# SENSORS.net
KiCad netlist of a schematic drawn in Altium Designer
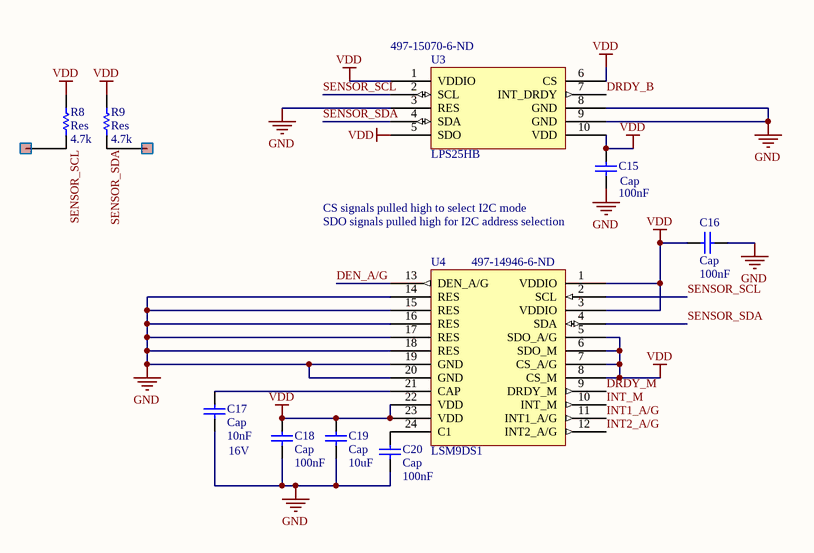
[diagram p0: SENSORS.SchDoc]

(export (version "E")
  (design (tool "Eeschema 10.0.6"))
  (components
    (comp (ref "C15")
      (value "Cap")
      (footprint "C0805")
      (description "Capacitor")
      (fields (field (name "ALTIUM_VALUE") "100nF") (field (name "PUBLISHER") "Altium Limited"))
      (libsource (lib "Capacitors") (part "Cap"))
    )
    (comp (ref "C16")
      (value "Cap")
      (footprint "C0805")
      (description "Capacitor")
      (fields (field (name "ALTIUM_VALUE") "100nF") (field (name "PUBLISHER") "Altium Limited"))
      (libsource (lib "Capacitors") (part "Cap"))
    )
    (comp (ref "C17")
      (value "Cap")
      (footprint "C0805")
      (description "Capacitor")
      (fields
        (field (name "ALTIUM_VALUE") "10nF")
        (field (name "RATING") "16V")
        (field (name "PUBLISHER") "Altium Limited")
      )
      (libsource (lib "Capacitors") (part "Cap"))
    )
    (comp (ref "C18")
      (value "Cap")
      (footprint "C0805")
      (description "Capacitor")
      (fields (field (name "ALTIUM_VALUE") "100nF") (field (name "PUBLISHER") "Altium Limited"))
      (libsource (lib "Capacitors") (part "Cap"))
    )
    (comp (ref "C19")
      (value "Cap")
      (footprint "C0805")
      (description "Capacitor")
      (fields (field (name "ALTIUM_VALUE") "10uF") (field (name "PUBLISHER") "Altium Limited"))
      (libsource (lib "Capacitors") (part "Cap"))
    )
    (comp (ref "C20")
      (value "Cap")
      (footprint "C0805")
      (description "Capacitor")
      (fields (field (name "ALTIUM_VALUE") "100nF") (field (name "PUBLISHER") "Altium Limited"))
      (libsource (lib "Capacitors") (part "Cap"))
    )
    (comp (ref "R8")
      (value "Res")
      (footprint "3216[1206]")
      (description "Surface Mount Resistor")
      (fields (field (name "ALTIUM_VALUE") "4.7k") (field (name "PUBLISHER") "Altium Limited"))
      (libsource (lib "Resistors") (part "Res"))
    )
    (comp (ref "R9")
      (value "Res")
      (footprint "3216[1206]")
      (description "Surface Mount Resistor")
      (fields (field (name "ALTIUM_VALUE") "4.7k") (field (name "PUBLISHER") "Altium Limited"))
      (libsource (lib "Resistors") (part "Res"))
    )
    (comp (ref "TPS1")
      (value "Test_point_SMD")
      (footprint "TEST_POINT_SMD")
      (description "Test Point SMD")
      (libsource (lib "FC") (part "Test_point_SMD"))
    )
    (comp (ref "TPS2")
      (value "Test_point_SMD")
      (footprint "TEST_POINT_SMD")
      (description "Test Point SMD")
      (libsource (lib "") (part "Test_point_SMD_1"))
    )
    (comp (ref "U3")
      (value "LPS25HB")
      (footprint "HLGA-10L - narrow")
      (fields
        (field (name "MANUFACTURER") "STMicroelectronics")
        (field (name "MANUFACTURER PART NUMBER") "LPS25HBTR")
        (field (name "SUPPLIER PART NUMBER 1") "497-15070-6-ND")
      )
      (libsource (lib "FC") (part "LPS25HB"))
    )
    (comp (ref "U4")
      (value "LSM9DS1")
      (footprint "LGA-24 - NARROW - Long Pads")
      (fields
        (field (name "MANUFACTURER") "STMicroelectronics")
        (field (name "MANUFACTURER PART NUMBER") "LSM9DS1TR")
        (field (name "SUPPLIER PART NUMBER 1") "497-14946-6-ND")
      )
      (libsource (lib "FC") (part "LSM9DS1"))
    )
  )
  (nets
    (net (code "1") (name "/DEN_A{slash}G") (class "Default")
      (node (ref "U4") (pin "13") (pinfunction "DEN_A/G_13") (pintype "output"))
    )
    (net (code "2") (name "/DRDY_B") (class "Default")
      (node (ref "U3") (pin "7") (pinfunction "INT_DRDY_7") (pintype "output"))
    )
    (net (code "3") (name "/DRDY_M") (class "Default")
      (node (ref "U4") (pin "9") (pinfunction "DRDY_M_9") (pintype "output"))
    )
    (net (code "4") (name "/INT1_A{slash}G") (class "Default")
      (node (ref "U4") (pin "11") (pinfunction "INT1_A/G_11") (pintype "output"))
    )
    (net (code "5") (name "/INT2_A{slash}G") (class "Default")
      (node (ref "U4") (pin "12") (pinfunction "INT2_A/G_12") (pintype "output"))
    )
    (net (code "6") (name "/INT_M") (class "Default")
      (node (ref "U4") (pin "10") (pinfunction "INT_M_10") (pintype "output"))
    )
    (net (code "7") (name "/SENSOR_SCL") (class "Default")
      (node (ref "R8") (pin "2") (pinfunction "2_2") (pintype "passive"))
      (node (ref "TPS1") (pin "1") (pinfunction "1_1") (pintype "tri_state"))
      (node (ref "U3") (pin "2") (pinfunction "SCL_2") (pintype "bidirectional"))
      (node (ref "U4") (pin "2") (pinfunction "SCL_2") (pintype "input"))
    )
    (net (code "8") (name "/SENSOR_SDA") (class "Default")
      (node (ref "R9") (pin "2") (pinfunction "2_2") (pintype "passive"))
      (node (ref "TPS2") (pin "1") (pinfunction "1_1") (pintype "tri_state"))
      (node (ref "U3") (pin "4") (pinfunction "SDA_4") (pintype "bidirectional"))
      (node (ref "U4") (pin "4") (pinfunction "SDA_4") (pintype "bidirectional"))
    )
    (net (code "9") (name "GND") (class "Default")
      (node (ref "C15") (pin "1") (pinfunction "1_1") (pintype "passive"))
      (node (ref "C16") (pin "2") (pinfunction "2_2") (pintype "passive"))
      (node (ref "C17") (pin "2") (pinfunction "2_2") (pintype "passive"))
      (node (ref "C18") (pin "2") (pinfunction "2_2") (pintype "passive"))
      (node (ref "C19") (pin "2") (pinfunction "2_2") (pintype "passive"))
      (node (ref "C20") (pin "1") (pinfunction "1_1") (pintype "passive"))
      (node (ref "U3") (pin "3") (pinfunction "RES_3") (pintype "power_in"))
      (node (ref "U3") (pin "8") (pinfunction "GND_8") (pintype "power_in"))
      (node (ref "U3") (pin "9") (pinfunction "GND_9") (pintype "power_in"))
      (node (ref "U4") (pin "14") (pinfunction "RES_14") (pintype "power_in"))
      (node (ref "U4") (pin "15") (pinfunction "RES_15") (pintype "power_in"))
      (node (ref "U4") (pin "16") (pinfunction "RES_16") (pintype "power_in"))
      (node (ref "U4") (pin "17") (pinfunction "RES_17") (pintype "power_in"))
      (node (ref "U4") (pin "18") (pinfunction "RES_18") (pintype "power_in"))
      (node (ref "U4") (pin "19") (pinfunction "GND_19") (pintype "power_in"))
      (node (ref "U4") (pin "20") (pinfunction "GND_20") (pintype "power_in"))
    )
    (net (code "10") (name "Net-(U4-C1)") (class "Default")
      (node (ref "C20") (pin "2") (pinfunction "2_2") (pintype "passive"))
      (node (ref "U4") (pin "24") (pinfunction "C1_24") (pintype "power_in"))
    )
    (net (code "11") (name "Net-(U4-CAP)") (class "Default")
      (node (ref "C17") (pin "1") (pinfunction "1_1") (pintype "passive"))
      (node (ref "U4") (pin "21") (pinfunction "CAP_21") (pintype "power_in"))
    )
    (net (code "12") (name "VDD") (class "Default")
      (node (ref "C15") (pin "2") (pinfunction "2_2") (pintype "passive"))
      (node (ref "C16") (pin "1") (pinfunction "1_1") (pintype "passive"))
      (node (ref "C18") (pin "1") (pinfunction "1_1") (pintype "passive"))
      (node (ref "C19") (pin "1") (pinfunction "1_1") (pintype "passive"))
      (node (ref "R8") (pin "1") (pinfunction "1_1") (pintype "passive"))
      (node (ref "R9") (pin "1") (pinfunction "1_1") (pintype "passive"))
      (node (ref "U3") (pin "1") (pinfunction "VDDIO_1") (pintype "power_in"))
      (node (ref "U3") (pin "10") (pinfunction "VDD_10") (pintype "power_in"))
      (node (ref "U3") (pin "5") (pinfunction "SDO_5") (pintype "power_in"))
      (node (ref "U3") (pin "6") (pinfunction "CS_6") (pintype "power_in"))
      (node (ref "U4") (pin "1") (pinfunction "VDDIO_1") (pintype "power_in"))
      (node (ref "U4") (pin "22") (pinfunction "VDD_22") (pintype "power_in"))
      (node (ref "U4") (pin "23") (pinfunction "VDD_23") (pintype "power_in"))
      (node (ref "U4") (pin "3") (pinfunction "VDDIO_3") (pintype "power_in"))
      (node (ref "U4") (pin "5") (pinfunction "SDO_A/G_5") (pintype "power_in"))
      (node (ref "U4") (pin "6") (pinfunction "SDO_M_6") (pintype "power_in"))
      (node (ref "U4") (pin "7") (pinfunction "CS_A/G_7") (pintype "power_in"))
      (node (ref "U4") (pin "8") (pinfunction "CS_M_8") (pintype "power_in"))
    )
  )
)
